# Ecu_1.net
KiCad netlist of a schematic drawn in EAGLE
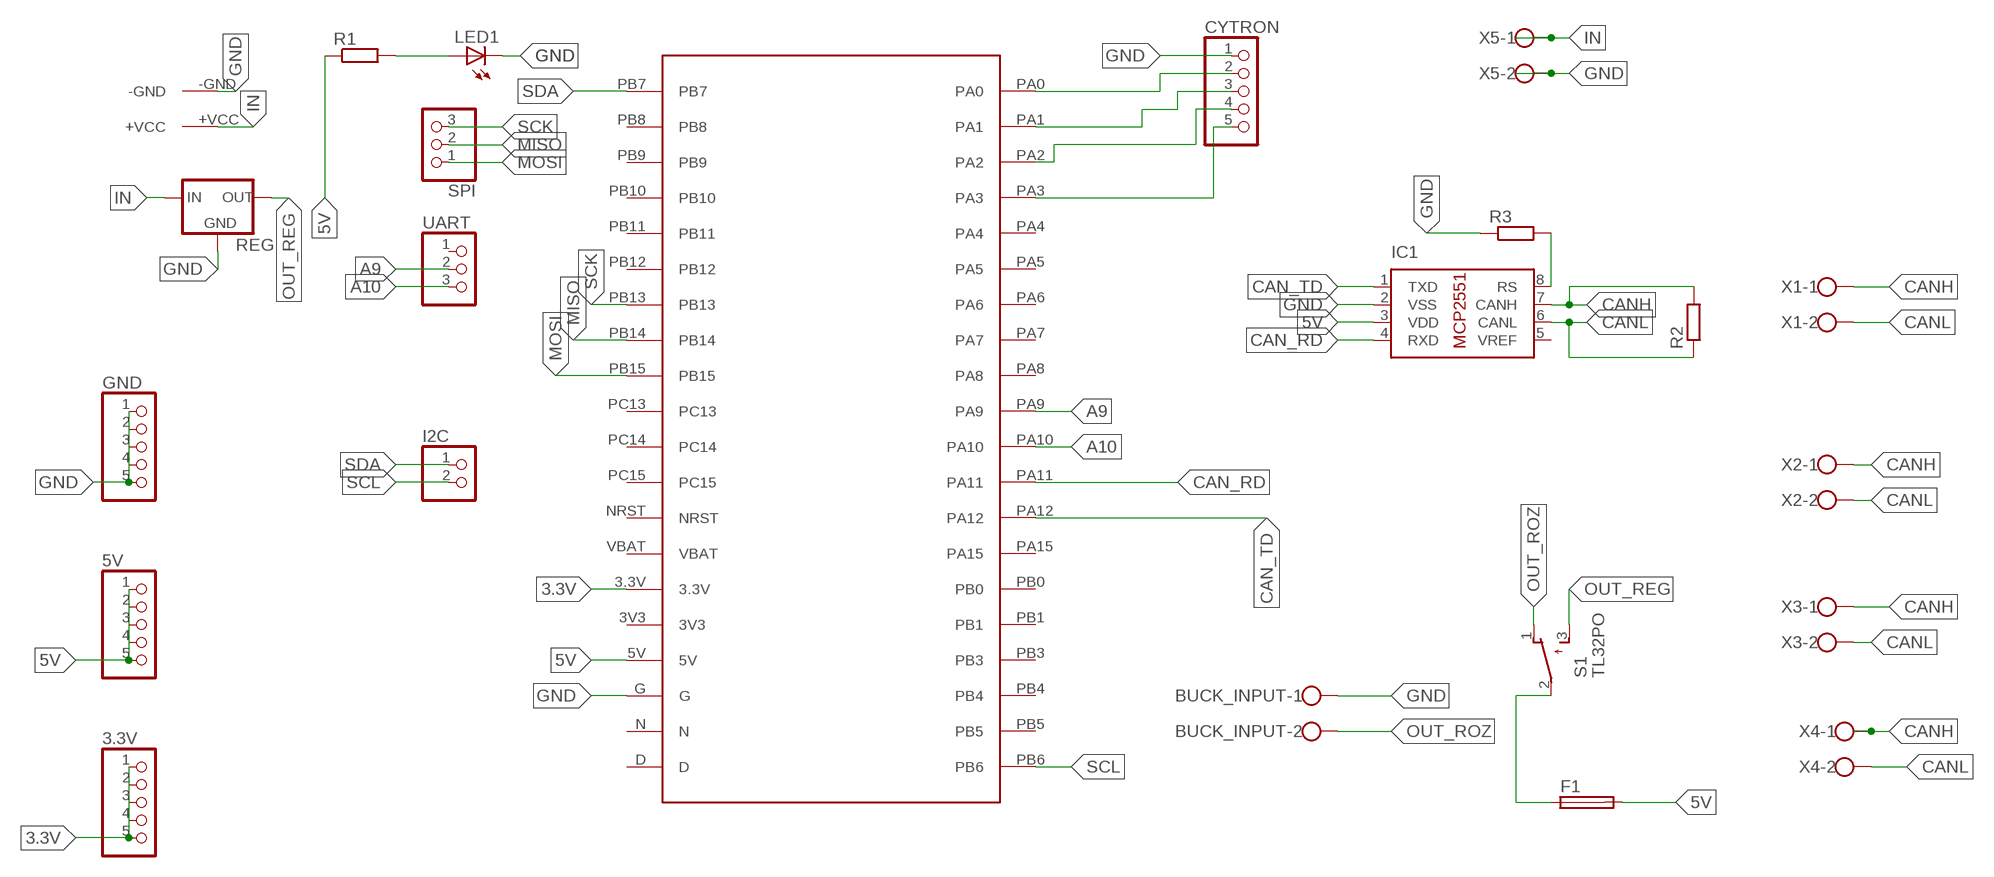
[diagram p0: schematic, sheet 1]

(export (version "E")
  (design (tool "Eeschema 10.0.6"))
  (components
    (comp (ref "3.3V")
      (value "PINHD-1X5")
      (footprint "eagle-import:1X05")
      (libsource (lib "eagle-import") (part "PINHD-1X5"))
    )
    (comp (ref "5V")
      (value "PINHD-1X5")
      (footprint "eagle-import:1X05")
      (libsource (lib "eagle-import") (part "PINHD-1X5"))
    )
    (comp (ref "BUCK_INPUT")
      (value "W237-102")
      (footprint "eagle-import:W237-102")
      (fields (field (name "MPN") "237-102"))
      (libsource (lib "eagle-import") (part "W237-102"))
    )
    (comp (ref "CYTRON")
      (value "PINHD-1X5")
      (footprint "eagle-import:1X05")
      (libsource (lib "eagle-import") (part "PINHD-1X5"))
    )
    (comp (ref "F1")
      (value "GSH15")
      (footprint "eagle-import:GSH15")
      (fields (field (name "MPN") "64900001039"))
      (libsource (lib "eagle-import") (part "GSH15"))
    )
    (comp (ref "GND")
      (value "PINHD-1X5")
      (footprint "eagle-import:1X05")
      (libsource (lib "eagle-import") (part "PINHD-1X5"))
    )
    (comp (ref "I2C")
      (value "PINHD-1X2")
      (footprint "eagle-import:1X02")
      (libsource (lib "eagle-import") (part "PINHD-1X2"))
    )
    (comp (ref "IC1")
      (value "MCP2551/P")
      (footprint "eagle-import:DIL08")
      (libsource (lib "eagle-import") (part "MCP2551/P"))
    )
    (comp (ref "LED1")
      (value "LED5MM")
      (footprint "eagle-import:LED5MM")
      (libsource (lib "eagle-import") (part "LED5MM"))
    )
    (comp (ref "MM1")
      (value "XT60")
      (footprint "eagle-import:XT60")
      (libsource (lib "eagle-import") (part "XT60"))
    )
    (comp (ref "R1")
      (value "R-EU_0207/10")
      (footprint "eagle-import:0207_10")
      (libsource (lib "eagle-import") (part "R-EU_0207/10"))
    )
    (comp (ref "R2")
      (value "R-EU_0207/10")
      (footprint "eagle-import:0207_10")
      (libsource (lib "eagle-import") (part "R-EU_0207/10"))
    )
    (comp (ref "R3")
      (value "R-EU_0207/10")
      (footprint "eagle-import:0207_10")
      (libsource (lib "eagle-import") (part "R-EU_0207/10"))
    )
    (comp (ref "REG")
      (value "78XXS")
      (footprint "eagle-import:78XXS")
      (libsource (lib "eagle-import") (part "78XXS"))
    )
    (comp (ref "S1")
      (value "TL32PO")
      (footprint "eagle-import:TL3XPO")
      (libsource (lib "eagle-import") (part "TL32PO"))
    )
    (comp (ref "SPI")
      (value "PINHD-1X3")
      (footprint "eagle-import:1X03")
      (libsource (lib "eagle-import") (part "PINHD-1X3"))
    )
    (comp (ref "U$3")
      (value "STM32F103C8")
      (footprint "eagle-import:DIP")
      (libsource (lib "eagle-import") (part "STM32F103C8"))
    )
    (comp (ref "UART")
      (value "PINHD-1X3")
      (footprint "eagle-import:1X03")
      (libsource (lib "eagle-import") (part "PINHD-1X3"))
    )
    (comp (ref "X1")
      (value "W237-102")
      (footprint "eagle-import:W237-102")
      (fields (field (name "MPN") "237-102"))
      (libsource (lib "eagle-import") (part "W237-102"))
    )
    (comp (ref "X2")
      (value "W237-102")
      (footprint "eagle-import:W237-102")
      (fields (field (name "MPN") "237-102"))
      (libsource (lib "eagle-import") (part "W237-102"))
    )
    (comp (ref "X3")
      (value "W237-102")
      (footprint "eagle-import:W237-102")
      (fields (field (name "MPN") "237-102"))
      (libsource (lib "eagle-import") (part "W237-102"))
    )
    (comp (ref "X4")
      (value "W237-102")
      (footprint "eagle-import:W237-102")
      (fields (field (name "MPN") "237-102"))
      (libsource (lib "eagle-import") (part "W237-102"))
    )
    (comp (ref "X5")
      (value "W237-102")
      (footprint "eagle-import:W237-102")
      (fields (field (name "MPN") "237-102"))
      (libsource (lib "eagle-import") (part "W237-102"))
    )
  )
  (nets
    (net (code "1") (name "3.3V") (class "Default")
      (node (ref "3.3V") (pin "1") (pinfunction "1_1") (pintype "passive"))
      (node (ref "3.3V") (pin "5") (pinfunction "5_5") (pintype "passive"))
      (node (ref "U$3") (pin "3.3V") (pinfunction "3.3V_3.3V") (pintype "bidirectional"))
    )
    (net (code "2") (name "5V") (class "Default")
      (node (ref "5V") (pin "1") (pinfunction "1_1") (pintype "passive"))
      (node (ref "5V") (pin "5") (pinfunction "5_5") (pintype "passive"))
      (node (ref "F1") (pin "2") (pinfunction "2_2") (pintype "passive"))
      (node (ref "IC1") (pin "3") (pinfunction "VDD_3") (pintype "power_in"))
      (node (ref "R1") (pin "1") (pinfunction "1_1") (pintype "passive"))
      (node (ref "U$3") (pin "5V") (pinfunction "5V_5V") (pintype "bidirectional"))
    )
    (net (code "3") (name "A9") (class "Default")
      (node (ref "U$3") (pin "PA9") (pinfunction "PA9_PA9") (pintype "bidirectional"))
      (node (ref "UART") (pin "2") (pinfunction "2_2") (pintype "passive"))
    )
    (net (code "4") (name "A10") (class "Default")
      (node (ref "U$3") (pin "PA10") (pinfunction "PA10_PA10") (pintype "bidirectional"))
      (node (ref "UART") (pin "3") (pinfunction "3_3") (pintype "passive"))
    )
    (net (code "5") (name "CANH") (class "Default")
      (node (ref "IC1") (pin "7") (pinfunction "CANH_7") (pintype "bidirectional"))
      (node (ref "R2") (pin "2") (pinfunction "2_2") (pintype "passive"))
      (node (ref "X1") (pin "1") (pinfunction "KL_1") (pintype "passive"))
      (node (ref "X2") (pin "1") (pinfunction "KL_1") (pintype "passive"))
      (node (ref "X3") (pin "1") (pinfunction "KL_1") (pintype "passive"))
      (node (ref "X4") (pin "1") (pinfunction "KL_1") (pintype "passive"))
    )
    (net (code "6") (name "CANL") (class "Default")
      (node (ref "IC1") (pin "6") (pinfunction "CANL_6") (pintype "bidirectional"))
      (node (ref "R2") (pin "1") (pinfunction "1_1") (pintype "passive"))
      (node (ref "X1") (pin "2") (pinfunction "KL_2") (pintype "passive"))
      (node (ref "X2") (pin "2") (pinfunction "KL_2") (pintype "passive"))
      (node (ref "X3") (pin "2") (pinfunction "KL_2") (pintype "passive"))
      (node (ref "X4") (pin "2") (pinfunction "KL_2") (pintype "passive"))
    )
    (net (code "7") (name "CAN_RD") (class "Default")
      (node (ref "IC1") (pin "4") (pinfunction "RXD_4") (pintype "output"))
      (node (ref "U$3") (pin "PA11") (pinfunction "PA11_PA11") (pintype "bidirectional"))
    )
    (net (code "8") (name "CAN_TD") (class "Default")
      (node (ref "IC1") (pin "1") (pinfunction "TXD_1") (pintype "input"))
      (node (ref "U$3") (pin "PA12") (pinfunction "PA12_PA12") (pintype "bidirectional"))
    )
    (net (code "9") (name "GND") (class "Default")
      (node (ref "BUCK_INPUT") (pin "1") (pinfunction "KL_1") (pintype "passive"))
      (node (ref "CYTRON") (pin "1") (pinfunction "1_1") (pintype "passive"))
      (node (ref "GND") (pin "1") (pinfunction "1_1") (pintype "passive"))
      (node (ref "GND") (pin "5") (pinfunction "5_5") (pintype "passive"))
      (node (ref "IC1") (pin "2") (pinfunction "VSS_2") (pintype "power_in"))
      (node (ref "LED1") (pin "K") (pinfunction "C_K") (pintype "passive"))
      (node (ref "MM1") (pin "-GND") (pinfunction "-GND_-GND") (pintype "input"))
      (node (ref "R3") (pin "1") (pinfunction "1_1") (pintype "passive"))
      (node (ref "REG") (pin "GND") (pinfunction "GND_GND") (pintype "input"))
      (node (ref "U$3") (pin "G") (pinfunction "G_G") (pintype "bidirectional"))
      (node (ref "X5") (pin "2") (pinfunction "KL_2") (pintype "passive"))
    )
    (net (code "10") (name "IN") (class "Default")
      (node (ref "MM1") (pin "+VCC") (pinfunction "+VCC_+VCC") (pintype "bidirectional"))
      (node (ref "REG") (pin "IN") (pinfunction "IN_IN") (pintype "input"))
      (node (ref "X5") (pin "1") (pinfunction "KL_1") (pintype "passive"))
    )
    (net (code "11") (name "MISO") (class "Default")
      (node (ref "SPI") (pin "2") (pinfunction "2_2") (pintype "passive"))
      (node (ref "U$3") (pin "PB14") (pinfunction "PB14_PB14") (pintype "bidirectional"))
    )
    (net (code "12") (name "MOSI") (class "Default")
      (node (ref "SPI") (pin "1") (pinfunction "1_1") (pintype "passive"))
      (node (ref "U$3") (pin "PB15") (pinfunction "PB15_PB15") (pintype "bidirectional"))
    )
    (net (code "13") (name "Net-(CYTRON-Pad2)") (class "Default")
      (node (ref "CYTRON") (pin "2") (pinfunction "2_2") (pintype "passive"))
      (node (ref "U$3") (pin "PA0") (pinfunction "PA0_PA0") (pintype "bidirectional"))
    )
    (net (code "14") (name "Net-(CYTRON-Pad3)") (class "Default")
      (node (ref "CYTRON") (pin "3") (pinfunction "3_3") (pintype "passive"))
      (node (ref "U$3") (pin "PA1") (pinfunction "PA1_PA1") (pintype "bidirectional"))
    )
    (net (code "15") (name "Net-(CYTRON-Pad4)") (class "Default")
      (node (ref "CYTRON") (pin "4") (pinfunction "4_4") (pintype "passive"))
      (node (ref "U$3") (pin "PA2") (pinfunction "PA2_PA2") (pintype "bidirectional"))
    )
    (net (code "16") (name "Net-(CYTRON-Pad5)") (class "Default")
      (node (ref "CYTRON") (pin "5") (pinfunction "5_5") (pintype "passive"))
      (node (ref "U$3") (pin "PA3") (pinfunction "PA3_PA3") (pintype "bidirectional"))
    )
    (net (code "17") (name "Net-(IC1-RS)") (class "Default")
      (node (ref "IC1") (pin "8") (pinfunction "RS_8") (pintype "input"))
      (node (ref "R3") (pin "2") (pinfunction "2_2") (pintype "passive"))
    )
    (net (code "18") (name "Net-(LED1-PadA)") (class "Default")
      (node (ref "LED1") (pin "A") (pinfunction "A_A") (pintype "passive"))
      (node (ref "R1") (pin "2") (pinfunction "2_2") (pintype "passive"))
    )
    (net (code "19") (name "Net-(S1-P)") (class "Default")
      (node (ref "F1") (pin "1") (pinfunction "1_1") (pintype "passive"))
      (node (ref "S1") (pin "2") (pinfunction "P_2") (pintype "passive"))
    )
    (net (code "20") (name "OUT_REG") (class "Default")
      (node (ref "REG") (pin "OUT") (pinfunction "OUT_OUT") (pintype "passive"))
      (node (ref "S1") (pin "3") (pinfunction "S_3") (pintype "passive"))
    )
    (net (code "21") (name "OUT_ROZ") (class "Default")
      (node (ref "BUCK_INPUT") (pin "2") (pinfunction "KL_2") (pintype "passive"))
      (node (ref "S1") (pin "1") (pinfunction "O_1") (pintype "passive"))
    )
    (net (code "22") (name "SCK") (class "Default")
      (node (ref "SPI") (pin "3") (pinfunction "3_3") (pintype "passive"))
      (node (ref "U$3") (pin "PB13") (pinfunction "PB13_PB13") (pintype "bidirectional"))
    )
    (net (code "23") (name "SCL") (class "Default")
      (node (ref "I2C") (pin "2") (pinfunction "2_2") (pintype "passive"))
      (node (ref "U$3") (pin "PB6") (pinfunction "PB6_PB6") (pintype "bidirectional"))
    )
    (net (code "24") (name "SDA") (class "Default")
      (node (ref "I2C") (pin "1") (pinfunction "1_1") (pintype "passive"))
      (node (ref "U$3") (pin "PB7") (pinfunction "PB7_PB7") (pintype "bidirectional"))
    )
    (net (code "25") (name "unconnected-(3.3V-Pad2)") (class "Default")
      (node (ref "3.3V") (pin "2") (pinfunction "2_2") (pintype "passive"))
    )
    (net (code "26") (name "unconnected-(3.3V-Pad3)") (class "Default")
      (node (ref "3.3V") (pin "3") (pinfunction "3_3") (pintype "passive"))
    )
    (net (code "27") (name "unconnected-(3.3V-Pad4)") (class "Default")
      (node (ref "3.3V") (pin "4") (pinfunction "4_4") (pintype "passive"))
    )
    (net (code "28") (name "unconnected-(5V-Pad2)") (class "Default")
      (node (ref "5V") (pin "2") (pinfunction "2_2") (pintype "passive"))
    )
    (net (code "29") (name "unconnected-(5V-Pad3)") (class "Default")
      (node (ref "5V") (pin "3") (pinfunction "3_3") (pintype "passive"))
    )
    (net (code "30") (name "unconnected-(5V-Pad4)") (class "Default")
      (node (ref "5V") (pin "4") (pinfunction "4_4") (pintype "passive"))
    )
    (net (code "31") (name "unconnected-(GND-Pad2)") (class "Default")
      (node (ref "GND") (pin "2") (pinfunction "2_2") (pintype "passive"))
    )
    (net (code "32") (name "unconnected-(GND-Pad3)") (class "Default")
      (node (ref "GND") (pin "3") (pinfunction "3_3") (pintype "passive"))
    )
    (net (code "33") (name "unconnected-(GND-Pad4)") (class "Default")
      (node (ref "GND") (pin "4") (pinfunction "4_4") (pintype "passive"))
    )
    (net (code "34") (name "unconnected-(IC1-VREF-Pad5)") (class "Default")
      (node (ref "IC1") (pin "5") (pinfunction "VREF_5") (pintype "output"))
    )
    (net (code "35") (name "unconnected-(U$3-Pad3V3)") (class "Default")
      (node (ref "U$3") (pin "3V3") (pinfunction "3V3_3V3") (pintype "bidirectional"))
    )
    (net (code "36") (name "unconnected-(U$3-PadD)") (class "Default")
      (node (ref "U$3") (pin "D") (pinfunction "D_D") (pintype "bidirectional"))
    )
    (net (code "37") (name "unconnected-(U$3-PadN)") (class "Default")
      (node (ref "U$3") (pin "N") (pinfunction "N_N") (pintype "bidirectional"))
    )
    (net (code "38") (name "unconnected-(U$3-PadNRST)") (class "Default")
      (node (ref "U$3") (pin "NRST") (pinfunction "NRST_NRST") (pintype "bidirectional"))
    )
    (net (code "39") (name "unconnected-(U$3-PadPA4)") (class "Default")
      (node (ref "U$3") (pin "PA4") (pinfunction "PA4_PA4") (pintype "bidirectional"))
    )
    (net (code "40") (name "unconnected-(U$3-PadPA5)") (class "Default")
      (node (ref "U$3") (pin "PA5") (pinfunction "PA5_PA5") (pintype "bidirectional"))
    )
    (net (code "41") (name "unconnected-(U$3-PadPA6)") (class "Default")
      (node (ref "U$3") (pin "PA6") (pinfunction "PA6_PA6") (pintype "bidirectional"))
    )
    (net (code "42") (name "unconnected-(U$3-PadPA7)") (class "Default")
      (node (ref "U$3") (pin "PA7") (pinfunction "PA7_PA7") (pintype "bidirectional"))
    )
    (net (code "43") (name "unconnected-(U$3-PadPA8)") (class "Default")
      (node (ref "U$3") (pin "PA8") (pinfunction "PA8_PA8") (pintype "bidirectional"))
    )
    (net (code "44") (name "unconnected-(U$3-PadPA15)") (class "Default")
      (node (ref "U$3") (pin "PA15") (pinfunction "PA15_PA15") (pintype "bidirectional"))
    )
    (net (code "45") (name "unconnected-(U$3-PadPB0)") (class "Default")
      (node (ref "U$3") (pin "PB0") (pinfunction "PB0_PB0") (pintype "bidirectional"))
    )
    (net (code "46") (name "unconnected-(U$3-PadPB1)") (class "Default")
      (node (ref "U$3") (pin "PB1") (pinfunction "PB1_PB1") (pintype "bidirectional"))
    )
    (net (code "47") (name "unconnected-(U$3-PadPB3)") (class "Default")
      (node (ref "U$3") (pin "PB3") (pinfunction "PB3_PB3") (pintype "bidirectional"))
    )
    (net (code "48") (name "unconnected-(U$3-PadPB4)") (class "Default")
      (node (ref "U$3") (pin "PB4") (pinfunction "PB4_PB4") (pintype "bidirectional"))
    )
    (net (code "49") (name "unconnected-(U$3-PadPB5)") (class "Default")
      (node (ref "U$3") (pin "PB5") (pinfunction "PB5_PB5") (pintype "bidirectional"))
    )
    (net (code "50") (name "unconnected-(U$3-PadPB8)") (class "Default")
      (node (ref "U$3") (pin "PB8") (pinfunction "PB8_PB8") (pintype "bidirectional"))
    )
    (net (code "51") (name "unconnected-(U$3-PadPB9)") (class "Default")
      (node (ref "U$3") (pin "PB9") (pinfunction "PB9_PB9") (pintype "bidirectional"))
    )
    (net (code "52") (name "unconnected-(U$3-PadPB10)") (class "Default")
      (node (ref "U$3") (pin "PB10") (pinfunction "PB10_PB10") (pintype "bidirectional"))
    )
    (net (code "53") (name "unconnected-(U$3-PadPB11)") (class "Default")
      (node (ref "U$3") (pin "PB11") (pinfunction "PB11_PB11") (pintype "bidirectional"))
    )
    (net (code "54") (name "unconnected-(U$3-PadPB12)") (class "Default")
      (node (ref "U$3") (pin "PB12") (pinfunction "PB12_PB12") (pintype "bidirectional"))
    )
    (net (code "55") (name "unconnected-(U$3-PadPC13)") (class "Default")
      (node (ref "U$3") (pin "PC13") (pinfunction "PC13_PC13") (pintype "bidirectional"))
    )
    (net (code "56") (name "unconnected-(U$3-PadPC14)") (class "Default")
      (node (ref "U$3") (pin "PC14") (pinfunction "PC14_PC14") (pintype "bidirectional"))
    )
    (net (code "57") (name "unconnected-(U$3-PadPC15)") (class "Default")
      (node (ref "U$3") (pin "PC15") (pinfunction "PC15_PC15") (pintype "bidirectional"))
    )
    (net (code "58") (name "unconnected-(U$3-PadVBAT)") (class "Default")
      (node (ref "U$3") (pin "VBAT") (pinfunction "VBAT_VBAT") (pintype "bidirectional"))
    )
    (net (code "59") (name "unconnected-(UART-Pad1)") (class "Default")
      (node (ref "UART") (pin "1") (pinfunction "1_1") (pintype "passive"))
    )
  )
)
